# in_voltage_ctl.net
KiCad netlist of a schematic drawn in EAGLE
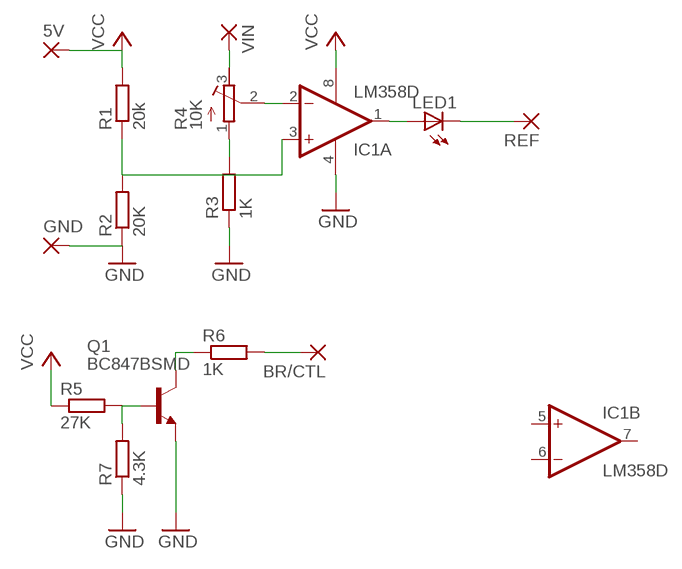
[diagram p0: schematic, sheet 1]

(export (version "E")
  (design (tool "Eeschema 10.0.6"))
  (components
    (comp (ref "5V")
      (value "SMD2")
      (footprint "eagle-import:SMD1,27-2,54")
      (libsource (lib "eagle-import") (part "SMD2"))
    )
    (comp (ref "BR/CTL")
      (value "SMD2")
      (footprint "eagle-import:SMD1,27-2,54")
      (libsource (lib "eagle-import") (part "SMD2"))
    )
    (comp (ref "GND")
      (value "SMD2")
      (footprint "eagle-import:SMD1,27-2,54")
      (libsource (lib "eagle-import") (part "SMD2"))
    )
    (comp (ref "IC1")
      (value "LM358D")
      (footprint "eagle-import:SO08")
      (libsource (lib "eagle-import") (part "LM358D"))
    )
    (comp (ref "LED1")
      (value "LEDSML0805")
      (footprint "eagle-import:SML0805")
      (libsource (lib "eagle-import") (part "LEDSML0805"))
    )
    (comp (ref "Q1")
      (value "BC847BSMD")
      (footprint "eagle-import:SOT23")
      (libsource (lib "eagle-import") (part "BC847SMDB"))
    )
    (comp (ref "R1")
      (value "20k")
      (footprint "eagle-import:R0805")
      (libsource (lib "eagle-import") (part "R-EU_R0805"))
    )
    (comp (ref "R2")
      (value "20K")
      (footprint "eagle-import:R0805")
      (libsource (lib "eagle-import") (part "R-EU_R0805"))
    )
    (comp (ref "R3")
      (value "1K")
      (footprint "eagle-import:R0805")
      (libsource (lib "eagle-import") (part "R-EU_R0805"))
    )
    (comp (ref "R4")
      (value "10K")
      (footprint "eagle-import:RTRIM3296W")
      (libsource (lib "eagle-import") (part "R-TRIMM3296W"))
    )
    (comp (ref "R5")
      (value "27K")
      (footprint "eagle-import:R0805")
      (libsource (lib "eagle-import") (part "R-EU_R0805"))
    )
    (comp (ref "R6")
      (value "1K")
      (footprint "eagle-import:R0805")
      (libsource (lib "eagle-import") (part "R-EU_R0805"))
    )
    (comp (ref "R7")
      (value "4.3K")
      (footprint "eagle-import:R0805")
      (libsource (lib "eagle-import") (part "R-EU_R0805"))
    )
    (comp (ref "REF")
      (value "SMD2")
      (footprint "eagle-import:SMD1,27-2,54")
      (libsource (lib "eagle-import") (part "SMD2"))
    )
    (comp (ref "VIN")
      (value "SMD2")
      (footprint "eagle-import:SMD1,27-2,54")
      (libsource (lib "eagle-import") (part "SMD2"))
    )
  )
  (nets
    (net (code "1") (name "GND") (class "Default")
      (node (ref "GND") (pin "1") (pinfunction "P_1") (pintype "passive"))
      (node (ref "IC1") (pin "4") (pinfunction "V-_4") (pintype "power_in"))
      (node (ref "Q1") (pin "2") (pinfunction "E_2") (pintype "passive"))
      (node (ref "R2") (pin "1") (pinfunction "1_1") (pintype "passive"))
      (node (ref "R3") (pin "1") (pinfunction "1_1") (pintype "passive"))
      (node (ref "R7") (pin "1") (pinfunction "1_1") (pintype "passive"))
    )
    (net (code "2") (name "Net-(BR/CTL-P)") (class "Default")
      (node (ref "BR/CTL") (pin "1") (pinfunction "P_1") (pintype "passive"))
      (node (ref "R6") (pin "2") (pinfunction "2_2") (pintype "passive"))
    )
    (net (code "3") (name "Net-(IC1A-+IN)") (class "Default")
      (node (ref "IC1") (pin "3") (pinfunction "+IN_3") (pintype "input"))
      (node (ref "R1") (pin "1") (pinfunction "1_1") (pintype "passive"))
      (node (ref "R2") (pin "2") (pinfunction "2_2") (pintype "passive"))
    )
    (net (code "4") (name "Net-(IC1A--IN)") (class "Default")
      (node (ref "IC1") (pin "2") (pinfunction "-IN_2") (pintype "input"))
      (node (ref "R4") (pin "2") (pinfunction "S_2") (pintype "passive"))
    )
    (net (code "5") (name "Net-(IC1A-OUT)") (class "Default")
      (node (ref "IC1") (pin "1") (pinfunction "OUT_1") (pintype "output"))
      (node (ref "LED1") (pin "A") (pinfunction "A_A") (pintype "passive"))
    )
    (net (code "6") (name "Net-(Q1-B)") (class "Default")
      (node (ref "Q1") (pin "1") (pinfunction "B_1") (pintype "passive"))
      (node (ref "R5") (pin "2") (pinfunction "2_2") (pintype "passive"))
      (node (ref "R7") (pin "2") (pinfunction "2_2") (pintype "passive"))
    )
    (net (code "7") (name "Net-(Q1-C)") (class "Default")
      (node (ref "Q1") (pin "3") (pinfunction "C_3") (pintype "passive"))
      (node (ref "R6") (pin "1") (pinfunction "1_1") (pintype "passive"))
    )
    (net (code "8") (name "Net-(R4-A)") (class "Default")
      (node (ref "R3") (pin "2") (pinfunction "2_2") (pintype "passive"))
      (node (ref "R4") (pin "1") (pinfunction "A_1") (pintype "passive"))
    )
    (net (code "9") (name "Net-(R4-E)") (class "Default")
      (node (ref "R4") (pin "3") (pinfunction "E_3") (pintype "passive"))
      (node (ref "VIN") (pin "1") (pinfunction "P_1") (pintype "passive"))
    )
    (net (code "10") (name "Net-(REF-P)") (class "Default")
      (node (ref "LED1") (pin "C") (pinfunction "C_C") (pintype "passive"))
      (node (ref "REF") (pin "1") (pinfunction "P_1") (pintype "passive"))
    )
    (net (code "11") (name "VCC") (class "Default")
      (node (ref "5V") (pin "1") (pinfunction "P_1") (pintype "passive"))
      (node (ref "IC1") (pin "8") (pinfunction "V+_8") (pintype "power_in"))
      (node (ref "R1") (pin "2") (pinfunction "2_2") (pintype "passive"))
      (node (ref "R5") (pin "1") (pinfunction "1_1") (pintype "passive"))
    )
    (net (code "12") (name "unconnected-(IC1B-+IN-Pad5)") (class "Default")
      (node (ref "IC1") (pin "5") (pinfunction "+IN_5") (pintype "input"))
    )
    (net (code "13") (name "unconnected-(IC1B--IN-Pad6)") (class "Default")
      (node (ref "IC1") (pin "6") (pinfunction "-IN_6") (pintype "input"))
    )
    (net (code "14") (name "unconnected-(IC1B-OUT-Pad7)") (class "Default")
      (node (ref "IC1") (pin "7") (pinfunction "OUT_7") (pintype "output"))
    )
  )
)
